# FPGA_02.net
KiCad netlist of a schematic drawn in Altium Designer
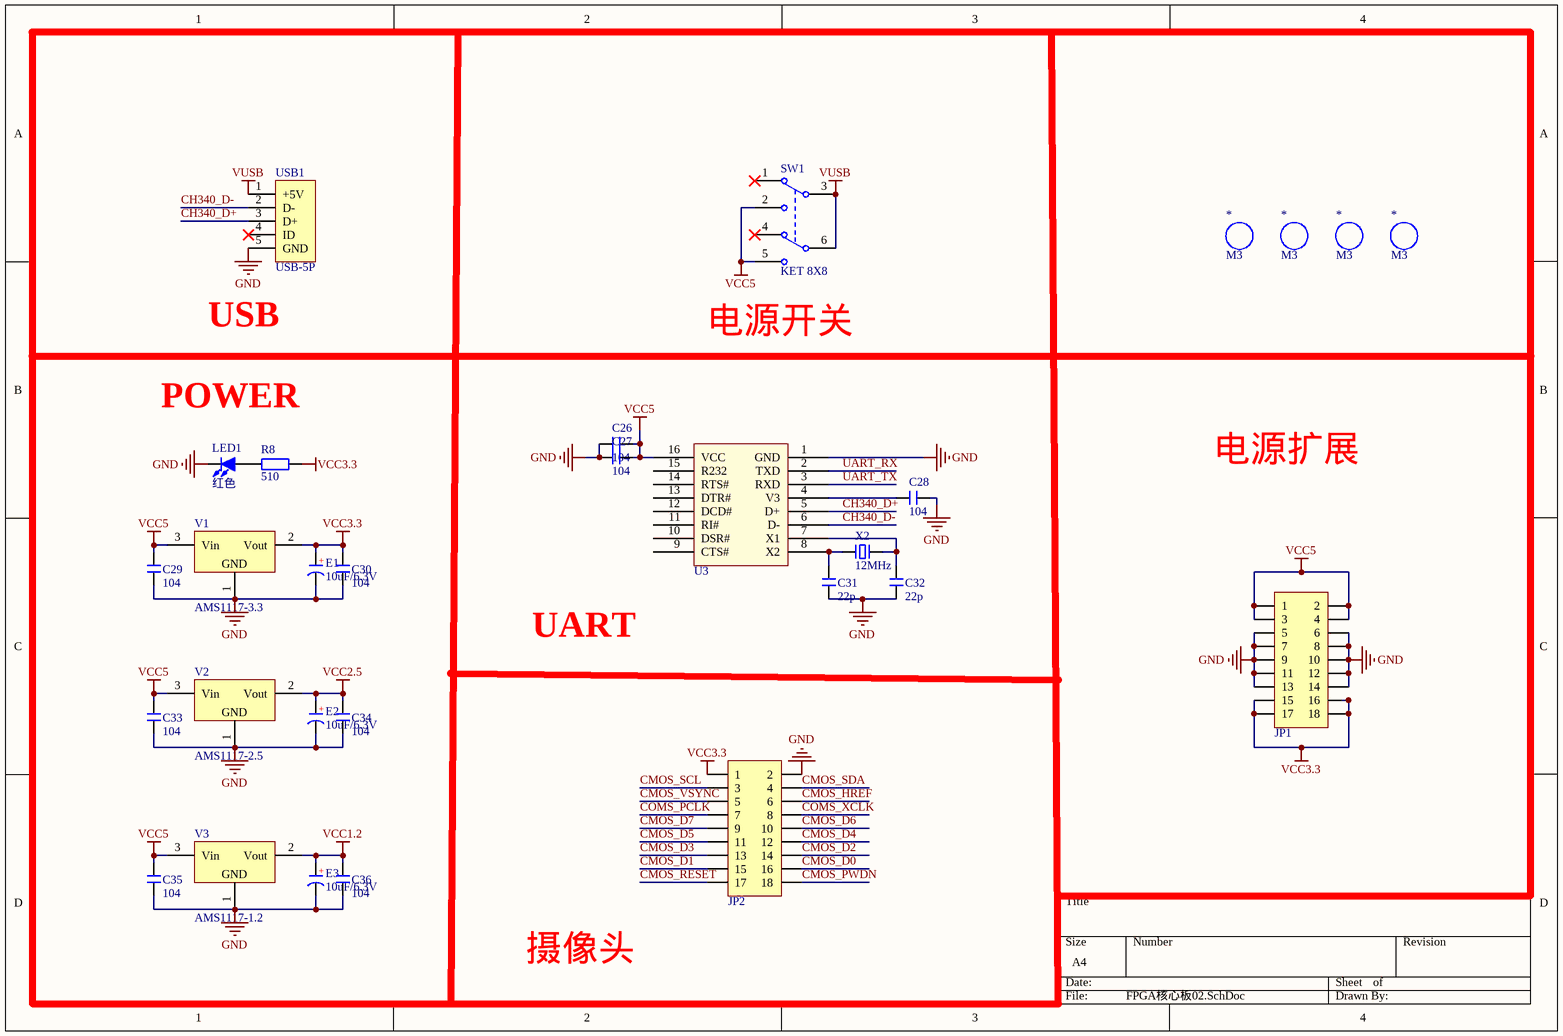
[diagram p0: FPGA核心板02.SchDoc]

(export (version "E")
  (design (tool "Eeschema 10.0.6"))
  (components
    (comp (ref "C26")
      (value "104")
      (footprint "C 0603_L")
      (description "贴片电容")
      (libsource (lib "0.1 - 电阻-电容-电感") (part "C"))
    )
    (comp (ref "C27")
      (value "104")
      (footprint "C 0603_L")
      (description "贴片电容")
      (libsource (lib "0.1 - 电阻-电容-电感") (part "C"))
    )
    (comp (ref "C28")
      (value "104")
      (footprint "C 0603_L")
      (description "贴片电容")
      (libsource (lib "0.1 - 电阻-电容-电感") (part "C"))
    )
    (comp (ref "C29")
      (value "104")
      (footprint "C 0603_L")
      (description "贴片电容")
      (libsource (lib "0.1 - 电阻-电容-电感") (part "C"))
    )
    (comp (ref "C30")
      (value "104")
      (footprint "C 0603_L")
      (description "贴片电容")
      (libsource (lib "0.1 - 电阻-电容-电感") (part "C"))
    )
    (comp (ref "C31")
      (value "22p")
      (footprint "C 0603_L")
      (description "贴片电容")
      (libsource (lib "0.1 - 电阻-电容-电感") (part "C"))
    )
    (comp (ref "C32")
      (value "22p")
      (footprint "C 0603_L")
      (description "贴片电容")
      (libsource (lib "0.1 - 电阻-电容-电感") (part "C"))
    )
    (comp (ref "C33")
      (value "104")
      (footprint "C 0603_L")
      (description "贴片电容")
      (libsource (lib "0.1 - 电阻-电容-电感") (part "C"))
    )
    (comp (ref "C34")
      (value "104")
      (footprint "C 0603_L")
      (description "贴片电容")
      (libsource (lib "0.1 - 电阻-电容-电感") (part "C"))
    )
    (comp (ref "C35")
      (value "104")
      (footprint "C 0603_L")
      (description "贴片电容")
      (libsource (lib "0.1 - 电阻-电容-电感") (part "C"))
    )
    (comp (ref "C36")
      (value "104")
      (footprint "C 0603_L")
      (description "贴片电容")
      (libsource (lib "0.1 - 电阻-电容-电感") (part "C"))
    )
    (comp (ref "E1")
      (value "10uF/6.3V")
      (footprint "CD A(3216)")
      (description "贴片钽电容")
      (libsource (lib "0.1 - 电阻-电容-电感") (part "CT"))
    )
    (comp (ref "E2")
      (value "10uF/6.3V")
      (footprint "CD A(3216)")
      (description "贴片钽电容")
      (libsource (lib "0.1 - 电阻-电容-电感") (part "CT"))
    )
    (comp (ref "E3")
      (value "10uF/6.3V")
      (footprint "CD A(3216)")
      (description "贴片钽电容")
      (libsource (lib "0.1 - 电阻-电容-电感") (part "CT"))
    )
    (comp (ref "JP1")
      (value "Header 9X2")
      (footprint "HDR2.54-LI-2x9P")
      (description "9*2P接插件")
      (fields (field (name "版权归属") "源创客"))
      (libsource (lib "5.3 - 接插件-脚距2.54 (100mil) ") (part "Header 9X2"))
    )
    (comp (ref "JP2")
      (value "Header 9X2")
      (footprint "HDR2.54-WI-2x9P")
      (description "9*2P接插件")
      (fields (field (name "版权归属") "源创客"))
      (libsource (lib "5.3 - 接插件-脚距2.54 (100mil) ") (part "Header 9X2"))
    )
    (comp (ref "LED1")
      (value "红色")
      (footprint "LED 0805B")
      (description "贴片LED")
      (fields (field (name "版权归属") "封装库来自淘宝 ID：黄晶宝石"))
      (libsource (lib "0.3 - LED发光二极管") (part "LED-SMD"))
    )
    (comp (ref "R8")
      (value "510")
      (footprint "R 0603_L")
      (description "贴片电阻")
      (fields (field (name "版权归属") "来自淘宝 ID：黄晶宝石"))
      (libsource (lib "0.1 - 电阻-电容-电感") (part "R"))
    )
    (comp (ref "SW1")
      (value "KET 8X8")
      (footprint "KFT DIP-8X8")
      (description "8*8自锁开关")
      (fields (field (name "版权归属") "封装库来自淘宝 ID：黄晶宝石"))
      (libsource (lib "0.7 - 常用按键-开关") (part "KET 8X8"))
    )
    (comp (ref "U3")
      (value "CH340G")
      (footprint "sop16_L")
      (libsource (lib "1.9 - CH341系列编程器芯片") (part "CH340G"))
    )
    (comp (ref "USB1")
      (value "USB-5P")
      (footprint "USB-MICRO_B")
      (description "微型USB母座")
      (libsource (lib "0.8 - 网口-音频插座") (part "USB-5P"))
    )
    (comp (ref "V1")
      (value "AMS1117-3.3")
      (footprint "SOT223_L")
      (description "三端稳压芯片")
      (libsource (lib "1.1 - 电源类芯片") (part "AMS1117"))
    )
    (comp (ref "V2")
      (value "AMS1117-2.5")
      (footprint "SOT223_L")
      (description "三端稳压芯片")
      (libsource (lib "1.1 - 电源类芯片") (part "AMS1117"))
    )
    (comp (ref "V3")
      (value "AMS1117-1.2")
      (footprint "SOT223_L")
      (description "三端稳压芯片")
      (libsource (lib "1.1 - 电源类芯片") (part "AMS1117"))
    )
    (comp (ref "X2")
      (value "12MHz")
      (footprint "OSC HC-49S")
      (description "2脚无源脚晶振")
      (fields (field (name "版权归属") "源创客"))
      (libsource (lib "2.0 - 保险丝-晶振-光耦") (part "XTAL-2P"))
    )
  )
  (nets
    (net (code "1") (name "/CH340_D+") (class "Default")
      (node (ref "U3") (pin "5") (pinfunction "D+_5") (pintype "passive"))
      (node (ref "USB1") (pin "3") (pinfunction "D+_3") (pintype "passive"))
    )
    (net (code "2") (name "/CH340_D-") (class "Default")
      (node (ref "U3") (pin "6") (pinfunction "D-_6") (pintype "passive"))
      (node (ref "USB1") (pin "2") (pinfunction "D-_2") (pintype "passive"))
    )
    (net (code "3") (name "/CMOS_D0") (class "Default")
      (node (ref "JP2") (pin "16") (pinfunction "16_16") (pintype "passive"))
    )
    (net (code "4") (name "/CMOS_D1") (class "Default")
      (node (ref "JP2") (pin "15") (pinfunction "15_15") (pintype "passive"))
    )
    (net (code "5") (name "/CMOS_D2") (class "Default")
      (node (ref "JP2") (pin "14") (pinfunction "14_14") (pintype "passive"))
    )
    (net (code "6") (name "/CMOS_D3") (class "Default")
      (node (ref "JP2") (pin "13") (pinfunction "13_13") (pintype "passive"))
    )
    (net (code "7") (name "/CMOS_D4") (class "Default")
      (node (ref "JP2") (pin "12") (pinfunction "12_12") (pintype "passive"))
    )
    (net (code "8") (name "/CMOS_D5") (class "Default")
      (node (ref "JP2") (pin "11") (pinfunction "11_11") (pintype "passive"))
    )
    (net (code "9") (name "/CMOS_D6") (class "Default")
      (node (ref "JP2") (pin "10") (pinfunction "10_10") (pintype "passive"))
    )
    (net (code "10") (name "/CMOS_D7") (class "Default")
      (node (ref "JP2") (pin "9") (pinfunction "9_9") (pintype "passive"))
    )
    (net (code "11") (name "/CMOS_HREF") (class "Default")
      (node (ref "JP2") (pin "6") (pinfunction "6_6") (pintype "passive"))
    )
    (net (code "12") (name "/CMOS_PWDN") (class "Default")
      (node (ref "JP2") (pin "18") (pinfunction "18_18") (pintype "passive"))
    )
    (net (code "13") (name "/CMOS_RESET") (class "Default")
      (node (ref "JP2") (pin "17") (pinfunction "17_17") (pintype "passive"))
    )
    (net (code "14") (name "/CMOS_SCL") (class "Default")
      (node (ref "JP2") (pin "3") (pinfunction "3_3") (pintype "passive"))
    )
    (net (code "15") (name "/CMOS_SDA") (class "Default")
      (node (ref "JP2") (pin "4") (pinfunction "4_4") (pintype "passive"))
    )
    (net (code "16") (name "/CMOS_VSYNC") (class "Default")
      (node (ref "JP2") (pin "5") (pinfunction "5_5") (pintype "passive"))
    )
    (net (code "17") (name "/COMS_PCLK") (class "Default")
      (node (ref "JP2") (pin "7") (pinfunction "7_7") (pintype "passive"))
    )
    (net (code "18") (name "/COMS_XCLK") (class "Default")
      (node (ref "JP2") (pin "8") (pinfunction "8_8") (pintype "passive"))
    )
    (net (code "19") (name "/UART_RX") (class "Default")
      (node (ref "U3") (pin "2") (pinfunction "TXD_2") (pintype "passive"))
    )
    (net (code "20") (name "/UART_TX") (class "Default")
      (node (ref "U3") (pin "3") (pinfunction "RXD_3") (pintype "passive"))
    )
    (net (code "21") (name "GND") (class "Default")
      (node (ref "C26") (pin "1") (pinfunction "1_1") (pintype "passive"))
      (node (ref "C27") (pin "1") (pinfunction "1_1") (pintype "passive"))
      (node (ref "C28") (pin "2") (pinfunction "2_2") (pintype "passive"))
      (node (ref "C29") (pin "2") (pinfunction "2_2") (pintype "passive"))
      (node (ref "C30") (pin "2") (pinfunction "2_2") (pintype "passive"))
      (node (ref "C31") (pin "1") (pinfunction "1_1") (pintype "passive"))
      (node (ref "C32") (pin "1") (pinfunction "1_1") (pintype "passive"))
      (node (ref "C33") (pin "2") (pinfunction "2_2") (pintype "passive"))
      (node (ref "C34") (pin "2") (pinfunction "2_2") (pintype "passive"))
      (node (ref "C35") (pin "1") (pinfunction "1_1") (pintype "passive"))
      (node (ref "C36") (pin "1") (pinfunction "1_1") (pintype "passive"))
      (node (ref "E1") (pin "2") (pinfunction "K_2") (pintype "passive"))
      (node (ref "E2") (pin "2") (pinfunction "K_2") (pintype "passive"))
      (node (ref "E3") (pin "2") (pinfunction "K_2") (pintype "passive"))
      (node (ref "JP1") (pin "10") (pinfunction "10_10") (pintype "passive"))
      (node (ref "JP1") (pin "11") (pinfunction "11_11") (pintype "passive"))
      (node (ref "JP1") (pin "12") (pinfunction "12_12") (pintype "passive"))
      (node (ref "JP1") (pin "13") (pinfunction "13_13") (pintype "passive"))
      (node (ref "JP1") (pin "14") (pinfunction "14_14") (pintype "passive"))
      (node (ref "JP1") (pin "5") (pinfunction "5_5") (pintype "passive"))
      (node (ref "JP1") (pin "6") (pinfunction "6_6") (pintype "passive"))
      (node (ref "JP1") (pin "7") (pinfunction "7_7") (pintype "passive"))
      (node (ref "JP1") (pin "8") (pinfunction "8_8") (pintype "passive"))
      (node (ref "JP1") (pin "9") (pinfunction "9_9") (pintype "passive"))
      (node (ref "JP2") (pin "2") (pinfunction "2_2") (pintype "passive"))
      (node (ref "LED1") (pin "2") (pinfunction "K_2") (pintype "passive"))
      (node (ref "U3") (pin "1") (pinfunction "GND_1") (pintype "passive"))
      (node (ref "USB1") (pin "5") (pinfunction "GND_5") (pintype "passive"))
      (node (ref "V1") (pin "1") (pinfunction "GND_1") (pintype "passive"))
      (node (ref "V2") (pin "1") (pinfunction "GND_1") (pintype "passive"))
      (node (ref "V3") (pin "1") (pinfunction "GND_1") (pintype "passive"))
    )
    (net (code "22") (name "Net-(LED1-A)") (class "Default")
      (node (ref "LED1") (pin "1") (pinfunction "A_1") (pintype "passive"))
      (node (ref "R8") (pin "1") (pinfunction "1_1") (pintype "passive"))
    )
    (net (code "23") (name "Net-(U3-V3)") (class "Default")
      (node (ref "C28") (pin "1") (pinfunction "1_1") (pintype "passive"))
      (node (ref "U3") (pin "4") (pinfunction "V3_4") (pintype "passive"))
    )
    (net (code "24") (name "Net-(U3-X1)") (class "Default")
      (node (ref "C32") (pin "2") (pinfunction "2_2") (pintype "passive"))
      (node (ref "U3") (pin "7") (pinfunction "X1_7") (pintype "passive"))
      (node (ref "X2") (pin "2") (pinfunction "2_2") (pintype "passive"))
    )
    (net (code "25") (name "Net-(U3-X2)") (class "Default")
      (node (ref "C31") (pin "2") (pinfunction "2_2") (pintype "passive"))
      (node (ref "U3") (pin "8") (pinfunction "X2_8") (pintype "passive"))
      (node (ref "X2") (pin "1") (pinfunction "1_1") (pintype "passive"))
    )
    (net (code "26") (name "VCC1.2") (class "Default")
      (node (ref "C36") (pin "2") (pinfunction "2_2") (pintype "passive"))
      (node (ref "E3") (pin "1") (pinfunction "A_1") (pintype "passive"))
      (node (ref "V3") (pin "2") (pinfunction "Vout_2") (pintype "passive"))
    )
    (net (code "27") (name "VCC2.5") (class "Default")
      (node (ref "C34") (pin "1") (pinfunction "1_1") (pintype "passive"))
      (node (ref "E2") (pin "1") (pinfunction "A_1") (pintype "passive"))
      (node (ref "V2") (pin "2") (pinfunction "Vout_2") (pintype "passive"))
    )
    (net (code "28") (name "VCC3.3") (class "Default")
      (node (ref "C30") (pin "1") (pinfunction "1_1") (pintype "passive"))
      (node (ref "E1") (pin "1") (pinfunction "A_1") (pintype "passive"))
      (node (ref "JP1") (pin "15") (pinfunction "15_15") (pintype "passive"))
      (node (ref "JP1") (pin "16") (pinfunction "16_16") (pintype "passive"))
      (node (ref "JP1") (pin "17") (pinfunction "17_17") (pintype "passive"))
      (node (ref "JP1") (pin "18") (pinfunction "18_18") (pintype "passive"))
      (node (ref "JP2") (pin "1") (pinfunction "1_1") (pintype "passive"))
      (node (ref "R8") (pin "2") (pinfunction "2_2") (pintype "passive"))
      (node (ref "V1") (pin "2") (pinfunction "Vout_2") (pintype "passive"))
    )
    (net (code "29") (name "VCC5") (class "Default")
      (node (ref "C26") (pin "2") (pinfunction "2_2") (pintype "passive"))
      (node (ref "C27") (pin "2") (pinfunction "2_2") (pintype "passive"))
      (node (ref "C29") (pin "1") (pinfunction "1_1") (pintype "passive"))
      (node (ref "C33") (pin "1") (pinfunction "1_1") (pintype "passive"))
      (node (ref "C35") (pin "2") (pinfunction "2_2") (pintype "passive"))
      (node (ref "JP1") (pin "1") (pinfunction "1_1") (pintype "passive"))
      (node (ref "JP1") (pin "2") (pinfunction "2_2") (pintype "passive"))
      (node (ref "JP1") (pin "3") (pinfunction "3_3") (pintype "passive"))
      (node (ref "JP1") (pin "4") (pinfunction "4_4") (pintype "passive"))
      (node (ref "SW1") (pin "2") (pinfunction "COM2_2") (pintype "passive"))
      (node (ref "SW1") (pin "5") (pinfunction "COM2_5") (pintype "passive"))
      (node (ref "U3") (pin "16") (pinfunction "VCC_16") (pintype "passive"))
      (node (ref "V1") (pin "3") (pinfunction "Vin_3") (pintype "passive"))
      (node (ref "V2") (pin "3") (pinfunction "Vin_3") (pintype "passive"))
      (node (ref "V3") (pin "3") (pinfunction "Vin_3") (pintype "passive"))
    )
    (net (code "30") (name "VUSB") (class "Default")
      (node (ref "SW1") (pin "3") (pinfunction "NO1_3") (pintype "passive"))
      (node (ref "SW1") (pin "6") (pinfunction "NC2_6") (pintype "passive"))
      (node (ref "USB1") (pin "1") (pinfunction "+5V_1") (pintype "passive"))
    )
    (net (code "31") (name "unconnected-(SW1-NC1-Pad1)") (class "Default")
      (node (ref "SW1") (pin "1") (pinfunction "NC1_1") (pintype "passive+no_connect"))
    )
    (net (code "32") (name "unconnected-(SW1-NO2-Pad4)") (class "Default")
      (node (ref "SW1") (pin "4") (pinfunction "NO2_4") (pintype "passive+no_connect"))
    )
    (net (code "33") (name "unconnected-(U3-CTS#-Pad9)") (class "Default")
      (node (ref "U3") (pin "9") (pinfunction "CTS#_9") (pintype "passive"))
    )
    (net (code "34") (name "unconnected-(U3-DCD#-Pad12)") (class "Default")
      (node (ref "U3") (pin "12") (pinfunction "DCD#_12") (pintype "passive"))
    )
    (net (code "35") (name "unconnected-(U3-DSR#-Pad10)") (class "Default")
      (node (ref "U3") (pin "10") (pinfunction "DSR#_10") (pintype "passive"))
    )
    (net (code "36") (name "unconnected-(U3-DTR#-Pad13)") (class "Default")
      (node (ref "U3") (pin "13") (pinfunction "DTR#_13") (pintype "passive"))
    )
    (net (code "37") (name "unconnected-(U3-R232-Pad15)") (class "Default")
      (node (ref "U3") (pin "15") (pinfunction "R232_15") (pintype "passive"))
    )
    (net (code "38") (name "unconnected-(U3-RI#-Pad11)") (class "Default")
      (node (ref "U3") (pin "11") (pinfunction "RI#_11") (pintype "passive"))
    )
    (net (code "39") (name "unconnected-(U3-RTS#-Pad14)") (class "Default")
      (node (ref "U3") (pin "14") (pinfunction "RTS#_14") (pintype "passive"))
    )
    (net (code "40") (name "unconnected-(USB1-ID-Pad4)") (class "Default")
      (node (ref "USB1") (pin "4") (pinfunction "ID_4") (pintype "passive+no_connect"))
    )
  )
)
